# Debug.net
KiCad netlist of a schematic drawn in Altium Designer
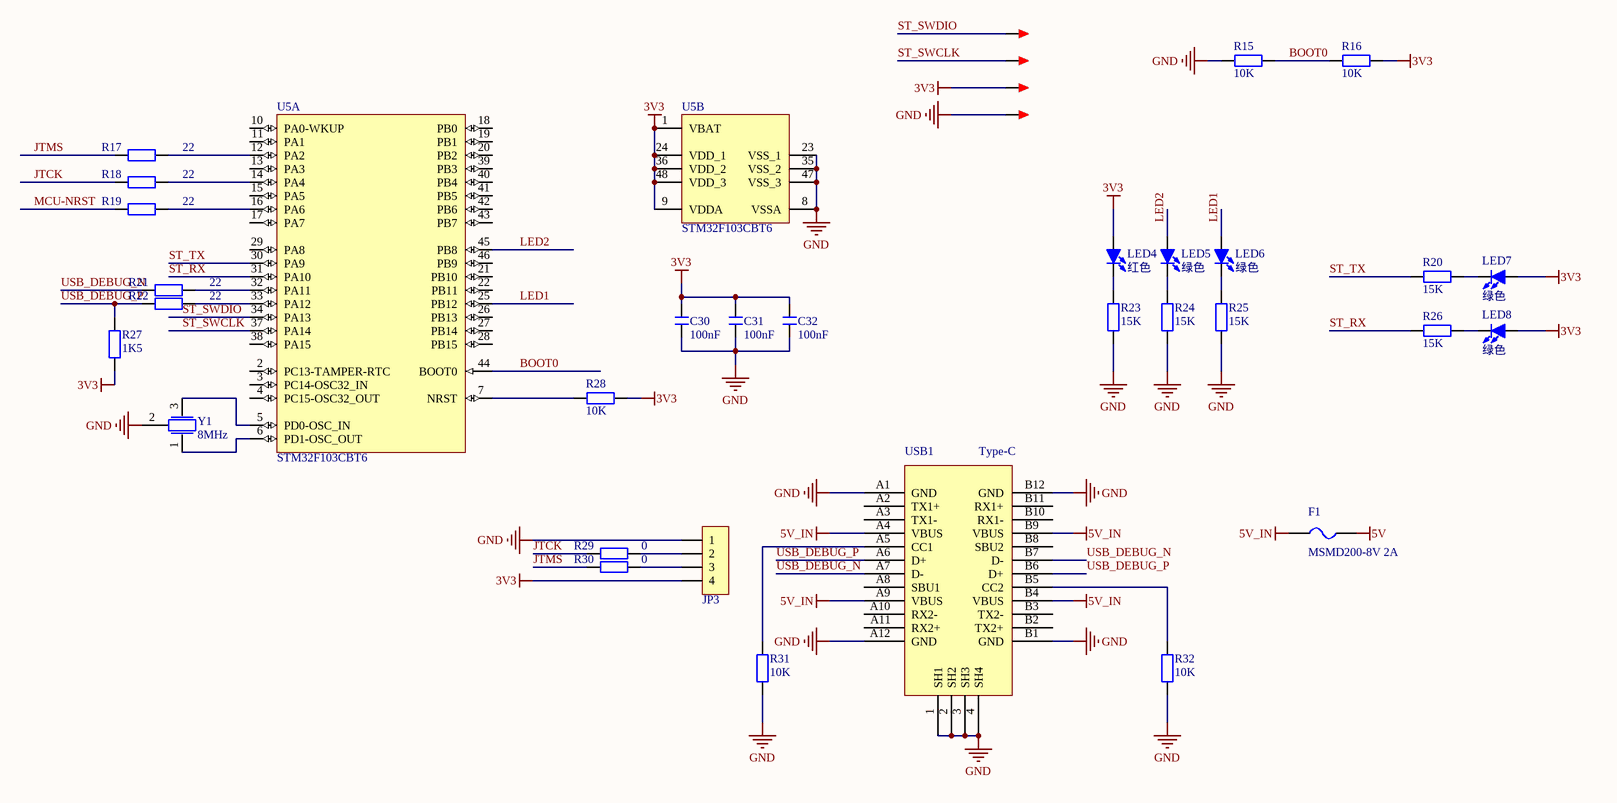
[diagram p0: Debug.SchDoc]

(export (version "E")
  (design (tool "Eeschema 10.0.6"))
  (components
    (comp (ref "C30")
      (value "100nF")
      (footprint "C 0402_L")
      (description "贴片电容")
      (libsource (lib "3.1   - 电阻-电容-电感") (part "C"))
    )
    (comp (ref "C31")
      (value "100nF")
      (footprint "C 0402_L")
      (description "贴片电容")
      (libsource (lib "3.1   - 电阻-电容-电感") (part "C"))
    )
    (comp (ref "C32")
      (value "100nF")
      (footprint "C 0402_L")
      (description "贴片电容")
      (libsource (lib "3.1   - 电阻-电容-电感") (part "C"))
    )
    (comp (ref "F1")
      (value "MSMD200-8V 2A")
      (footprint "FU 0603")
      (description "贴片保险丝")
      (libsource (lib "10.1 - 保险丝-晶振") (part "FU"))
    )
    (comp (ref "JP3")
      (value "HDR-1X4")
      (footprint "HDR2.54-WI-4P")
      (description "4P接插件")
      (libsource (lib "4.5   - 接插件-脚距2.54") (part "Header 4"))
    )
    (comp (ref "LED4")
      (value "红色")
      (footprint "LED")
      (description "C84267")
      (libsource (lib "9.1   - LED") (part "LED-SMD"))
    )
    (comp (ref "LED5")
      (value "绿色")
      (footprint "LED")
      (description "C84267")
      (libsource (lib "9.1   - LED") (part "LED-SMD"))
    )
    (comp (ref "LED6")
      (value "绿色")
      (footprint "LED")
      (description "C84267")
      (libsource (lib "9.1   - LED") (part "LED-SMD"))
    )
    (comp (ref "LED7")
      (value "绿色")
      (footprint "LED")
      (description "C84267")
      (libsource (lib "9.1   - LED") (part "LED-SMD"))
    )
    (comp (ref "LED8")
      (value "绿色")
      (footprint "LED")
      (description "C84267")
      (libsource (lib "9.1   - LED") (part "LED-SMD"))
    )
    (comp (ref "R15")
      (value "10K")
      (footprint "R 0402_L")
      (description "贴片电阻")
      (libsource (lib "3.1   - 电阻-电容-电感") (part "R"))
    )
    (comp (ref "R16")
      (value "10K")
      (footprint "R 0402_L")
      (description "贴片电阻")
      (libsource (lib "3.1   - 电阻-电容-电感") (part "R"))
    )
    (comp (ref "R17")
      (value "22")
      (footprint "R 0402_L")
      (description "贴片电阻")
      (libsource (lib "3.1   - 电阻-电容-电感") (part "R"))
    )
    (comp (ref "R18")
      (value "22")
      (footprint "R 0402_L")
      (description "贴片电阻")
      (libsource (lib "3.1   - 电阻-电容-电感") (part "R"))
    )
    (comp (ref "R19")
      (value "22")
      (footprint "R 0402_L")
      (description "贴片电阻")
      (libsource (lib "3.1   - 电阻-电容-电感") (part "R"))
    )
    (comp (ref "R20")
      (value "15K")
      (footprint "R 0402_L")
      (description "贴片电阻 0402 5%")
      (libsource (lib "3.1   - 电阻-电容-电感") (part "R"))
    )
    (comp (ref "R21")
      (value "22")
      (footprint "R 0402_L")
      (description "贴片电阻")
      (libsource (lib "3.1   - 电阻-电容-电感") (part "R"))
    )
    (comp (ref "R22")
      (value "22")
      (footprint "R 0402_L")
      (description "贴片电阻")
      (libsource (lib "3.1   - 电阻-电容-电感") (part "R"))
    )
    (comp (ref "R23")
      (value "15K")
      (footprint "R 0402_L")
      (description "贴片电阻 0402 5%")
      (libsource (lib "3.1   - 电阻-电容-电感") (part "R"))
    )
    (comp (ref "R24")
      (value "15K")
      (footprint "R 0402_L")
      (description "贴片电阻 0402 5%")
      (libsource (lib "3.1   - 电阻-电容-电感") (part "R"))
    )
    (comp (ref "R25")
      (value "15K")
      (footprint "R 0402_L")
      (description "贴片电阻 0402 5%")
      (libsource (lib "3.1   - 电阻-电容-电感") (part "R"))
    )
    (comp (ref "R26")
      (value "15K")
      (footprint "R 0402_L")
      (description "贴片电阻 0402 5%")
      (libsource (lib "3.1   - 电阻-电容-电感") (part "R"))
    )
    (comp (ref "R27")
      (value "1K5")
      (footprint "R 0402_L")
      (description "贴片电阻")
      (libsource (lib "3.1   - 电阻-电容-电感") (part "R"))
    )
    (comp (ref "R28")
      (value "10K")
      (footprint "R 0402_L")
      (description "贴片电阻")
      (libsource (lib "3.1   - 电阻-电容-电感") (part "R"))
    )
    (comp (ref "R29")
      (value "0")
      (footprint "R 0402_L")
      (description "贴片电阻")
      (libsource (lib "3.1   - 电阻-电容-电感") (part "R"))
    )
    (comp (ref "R30")
      (value "0")
      (footprint "R 0402_L")
      (description "贴片电阻")
      (libsource (lib "3.1   - 电阻-电容-电感") (part "R"))
    )
    (comp (ref "R31")
      (value "10K")
      (footprint "R 0402_L")
      (description "贴片电阻")
      (libsource (lib "3.1   - 电阻-电容-电感") (part "R"))
    )
    (comp (ref "R32")
      (value "10K")
      (footprint "R 0402_L")
      (description "贴片电阻")
      (libsource (lib "3.1   - 电阻-电容-电感") (part "R"))
    )
    (comp (ref "TP1")
      (value "TEST")
      (footprint "TEST 1.2")
      (description "测试点")
      (libsource (lib "15.1 - 未分类器件") (part "TEST"))
    )
    (comp (ref "TP2")
      (value "TEST")
      (footprint "TEST 1.2")
      (description "测试点")
      (libsource (lib "15.1 - 未分类器件") (part "TEST"))
    )
    (comp (ref "TP3")
      (value "TEST")
      (footprint "TEST 1.2")
      (description "测试点")
      (libsource (lib "15.1 - 未分类器件") (part "TEST"))
    )
    (comp (ref "TP4")
      (value "TEST")
      (footprint "TEST 1.2")
      (description "测试点")
      (libsource (lib "15.1 - 未分类器件") (part "TEST"))
    )
    (comp (ref "U5")
      (value "STM32F103CBT6")
      (footprint "LQFP48-7*7")
      (libsource (lib "STMicroelectronics STM32 F1") (part "STM32F103CBT6"))
    )
    (comp (ref "USB1")
      (value "Type-C")
      (footprint "Type-c接口")
      (libsource (lib "MyPcbLib") (part "USB-Type-C-TOP"))
    )
    (comp (ref "Y1")
      (value "8MHz")
      (footprint "三脚晶振")
      (description "村田贴片")
      (libsource (lib "MyPcbLib") (part "晶振-3Pin"))
    )
  )
  (nets
    (net (code "1") (name "/BOOT0") (class "Default")
      (node (ref "R15") (pin "2") (pinfunction "2_2") (pintype "passive"))
      (node (ref "R16") (pin "2") (pinfunction "2_2") (pintype "passive"))
      (node (ref "U5") (pin "44") (pinfunction "BOOT0_44") (pintype "input"))
    )
    (net (code "2") (name "/JTCK") (class "Default")
      (node (ref "R18") (pin "2") (pinfunction "2_2") (pintype "passive"))
      (node (ref "R29") (pin "1") (pinfunction "1_1") (pintype "passive"))
    )
    (net (code "3") (name "/JTMS") (class "Default")
      (node (ref "R17") (pin "2") (pinfunction "2_2") (pintype "passive"))
      (node (ref "R30") (pin "1") (pinfunction "1_1") (pintype "passive"))
    )
    (net (code "4") (name "/LED1") (class "Default")
      (node (ref "LED6") (pin "1") (pinfunction "A_1") (pintype "passive"))
      (node (ref "U5") (pin "25") (pinfunction "PB12_25") (pintype "bidirectional"))
    )
    (net (code "5") (name "/LED2") (class "Default")
      (node (ref "LED5") (pin "1") (pinfunction "A_1") (pintype "passive"))
      (node (ref "U5") (pin "45") (pinfunction "PB8_45") (pintype "bidirectional"))
    )
    (net (code "6") (name "/MCU-NRST") (class "Default")
      (node (ref "R19") (pin "2") (pinfunction "2_2") (pintype "passive"))
    )
    (net (code "7") (name "/ST_RX") (class "Default")
      (node (ref "R26") (pin "1") (pinfunction "1_1") (pintype "passive"))
      (node (ref "U5") (pin "31") (pinfunction "PA10_31") (pintype "bidirectional"))
    )
    (net (code "8") (name "/ST_SWCLK") (class "Default")
      (node (ref "TP2") (pin "1") (pinfunction "1_1") (pintype "passive"))
      (node (ref "U5") (pin "37") (pinfunction "PA14_37") (pintype "bidirectional"))
    )
    (net (code "9") (name "/ST_SWDIO") (class "Default")
      (node (ref "TP1") (pin "1") (pinfunction "1_1") (pintype "passive"))
      (node (ref "U5") (pin "34") (pinfunction "PA13_34") (pintype "bidirectional"))
    )
    (net (code "10") (name "/ST_TX") (class "Default")
      (node (ref "R20") (pin "1") (pinfunction "1_1") (pintype "passive"))
      (node (ref "U5") (pin "30") (pinfunction "PA9_30") (pintype "bidirectional"))
    )
    (net (code "11") (name "/USB_DEBUG_N") (class "Default")
      (node (ref "R21") (pin "2") (pinfunction "2_2") (pintype "passive"))
      (node (ref "USB1") (pin "A7") (pinfunction "D-_A7") (pintype "passive"))
      (node (ref "USB1") (pin "B7") (pinfunction "D-_B7") (pintype "passive"))
    )
    (net (code "12") (name "/USB_DEBUG_P") (class "Default")
      (node (ref "R22") (pin "2") (pinfunction "2_2") (pintype "passive"))
      (node (ref "R27") (pin "1") (pinfunction "1_1") (pintype "passive"))
      (node (ref "USB1") (pin "A6") (pinfunction "D+_A6") (pintype "passive"))
      (node (ref "USB1") (pin "B6") (pinfunction "D+_B6") (pintype "passive"))
    )
    (net (code "13") (name "3V3") (class "Default")
      (node (ref "C30") (pin "2") (pinfunction "2_2") (pintype "passive"))
      (node (ref "C31") (pin "2") (pinfunction "2_2") (pintype "passive"))
      (node (ref "C32") (pin "2") (pinfunction "2_2") (pintype "passive"))
      (node (ref "JP3") (pin "4") (pinfunction "4_4") (pintype "passive"))
      (node (ref "LED4") (pin "1") (pinfunction "A_1") (pintype "passive"))
      (node (ref "LED7") (pin "1") (pinfunction "A_1") (pintype "passive"))
      (node (ref "LED8") (pin "1") (pinfunction "A_1") (pintype "passive"))
      (node (ref "R16") (pin "1") (pinfunction "1_1") (pintype "passive"))
      (node (ref "R27") (pin "2") (pinfunction "2_2") (pintype "passive"))
      (node (ref "R28") (pin "1") (pinfunction "1_1") (pintype "passive"))
      (node (ref "TP3") (pin "1") (pinfunction "1_1") (pintype "passive"))
      (node (ref "U5") (pin "1") (pinfunction "VBAT_1") (pintype "power_in"))
      (node (ref "U5") (pin "24") (pinfunction "VDD_1_24") (pintype "power_in"))
      (node (ref "U5") (pin "36") (pinfunction "VDD_2_36") (pintype "power_in"))
      (node (ref "U5") (pin "48") (pinfunction "VDD_3_48") (pintype "power_in"))
      (node (ref "U5") (pin "9") (pinfunction "VDDA_9") (pintype "power_in"))
    )
    (net (code "14") (name "5V") (class "Default")
      (node (ref "F1") (pin "2") (pinfunction "2_2") (pintype "passive"))
    )
    (net (code "15") (name "5V_IN") (class "Default")
      (node (ref "F1") (pin "1") (pinfunction "1_1") (pintype "passive"))
      (node (ref "USB1") (pin "A4") (pinfunction "VBUS_A4") (pintype "passive"))
      (node (ref "USB1") (pin "A9") (pinfunction "VBUS_A9") (pintype "passive"))
      (node (ref "USB1") (pin "B4") (pinfunction "VBUS_B4") (pintype "passive"))
      (node (ref "USB1") (pin "B9") (pinfunction "VBUS_B9") (pintype "passive"))
    )
    (net (code "16") (name "GND") (class "Default")
      (node (ref "C30") (pin "1") (pinfunction "1_1") (pintype "passive"))
      (node (ref "C31") (pin "1") (pinfunction "1_1") (pintype "passive"))
      (node (ref "C32") (pin "1") (pinfunction "1_1") (pintype "passive"))
      (node (ref "JP3") (pin "1") (pinfunction "1_1") (pintype "passive"))
      (node (ref "R15") (pin "1") (pinfunction "1_1") (pintype "passive"))
      (node (ref "R23") (pin "1") (pinfunction "1_1") (pintype "passive"))
      (node (ref "R24") (pin "1") (pinfunction "1_1") (pintype "passive"))
      (node (ref "R25") (pin "1") (pinfunction "1_1") (pintype "passive"))
      (node (ref "R31") (pin "1") (pinfunction "1_1") (pintype "passive"))
      (node (ref "R32") (pin "1") (pinfunction "1_1") (pintype "passive"))
      (node (ref "TP4") (pin "1") (pinfunction "1_1") (pintype "passive"))
      (node (ref "U5") (pin "23") (pinfunction "VSS_1_23") (pintype "power_in"))
      (node (ref "U5") (pin "35") (pinfunction "VSS_2_35") (pintype "power_in"))
      (node (ref "U5") (pin "47") (pinfunction "VSS_3_47") (pintype "power_in"))
      (node (ref "U5") (pin "8") (pinfunction "VSSA_8") (pintype "power_in"))
      (node (ref "USB1") (pin "1") (pinfunction "SH1_1") (pintype "passive"))
      (node (ref "USB1") (pin "2") (pinfunction "SH2_2") (pintype "passive"))
      (node (ref "USB1") (pin "3") (pinfunction "SH3_3") (pintype "passive"))
      (node (ref "USB1") (pin "4") (pinfunction "SH4_4") (pintype "passive"))
      (node (ref "USB1") (pin "A1") (pinfunction "GND_A1") (pintype "passive"))
      (node (ref "USB1") (pin "A12") (pinfunction "GND_A12") (pintype "passive"))
      (node (ref "USB1") (pin "B1") (pinfunction "GND_B1") (pintype "passive"))
      (node (ref "USB1") (pin "B12") (pinfunction "GND_B12") (pintype "passive"))
      (node (ref "Y1") (pin "2") (pinfunction "2_2") (pintype "passive"))
    )
    (net (code "17") (name "Net-(JP3-Pad2)") (class "Default")
      (node (ref "JP3") (pin "2") (pinfunction "2_2") (pintype "passive"))
      (node (ref "R29") (pin "2") (pinfunction "2_2") (pintype "passive"))
    )
    (net (code "18") (name "Net-(JP3-Pad3)") (class "Default")
      (node (ref "JP3") (pin "3") (pinfunction "3_3") (pintype "passive"))
      (node (ref "R30") (pin "2") (pinfunction "2_2") (pintype "passive"))
    )
    (net (code "19") (name "Net-(LED4-K)") (class "Default")
      (node (ref "LED4") (pin "2") (pinfunction "K_2") (pintype "passive"))
      (node (ref "R23") (pin "2") (pinfunction "2_2") (pintype "passive"))
    )
    (net (code "20") (name "Net-(LED5-K)") (class "Default")
      (node (ref "LED5") (pin "2") (pinfunction "K_2") (pintype "passive"))
      (node (ref "R24") (pin "2") (pinfunction "2_2") (pintype "passive"))
    )
    (net (code "21") (name "Net-(LED6-K)") (class "Default")
      (node (ref "LED6") (pin "2") (pinfunction "K_2") (pintype "passive"))
      (node (ref "R25") (pin "2") (pinfunction "2_2") (pintype "passive"))
    )
    (net (code "22") (name "Net-(LED7-K)") (class "Default")
      (node (ref "LED7") (pin "2") (pinfunction "K_2") (pintype "passive"))
      (node (ref "R20") (pin "2") (pinfunction "2_2") (pintype "passive"))
    )
    (net (code "23") (name "Net-(LED8-K)") (class "Default")
      (node (ref "LED8") (pin "2") (pinfunction "K_2") (pintype "passive"))
      (node (ref "R26") (pin "2") (pinfunction "2_2") (pintype "passive"))
    )
    (net (code "24") (name "Net-(U5A-NRST)") (class "Default")
      (node (ref "R28") (pin "2") (pinfunction "2_2") (pintype "passive"))
      (node (ref "U5") (pin "7") (pinfunction "NRST_7") (pintype "bidirectional"))
    )
    (net (code "25") (name "Net-(U5A-PA2)") (class "Default")
      (node (ref "R17") (pin "1") (pinfunction "1_1") (pintype "passive"))
      (node (ref "U5") (pin "12") (pinfunction "PA2_12") (pintype "bidirectional"))
    )
    (net (code "26") (name "Net-(U5A-PA4)") (class "Default")
      (node (ref "R18") (pin "1") (pinfunction "1_1") (pintype "passive"))
      (node (ref "U5") (pin "14") (pinfunction "PA4_14") (pintype "bidirectional"))
    )
    (net (code "27") (name "Net-(U5A-PA6)") (class "Default")
      (node (ref "R19") (pin "1") (pinfunction "1_1") (pintype "passive"))
      (node (ref "U5") (pin "16") (pinfunction "PA6_16") (pintype "bidirectional"))
    )
    (net (code "28") (name "Net-(U5A-PA11)") (class "Default")
      (node (ref "R21") (pin "1") (pinfunction "1_1") (pintype "passive"))
      (node (ref "U5") (pin "32") (pinfunction "PA11_32") (pintype "bidirectional"))
    )
    (net (code "29") (name "Net-(U5A-PA12)") (class "Default")
      (node (ref "R22") (pin "1") (pinfunction "1_1") (pintype "passive"))
      (node (ref "U5") (pin "33") (pinfunction "PA12_33") (pintype "bidirectional"))
    )
    (net (code "30") (name "Net-(U5A-PD0-OSC_IN)") (class "Default")
      (node (ref "U5") (pin "5") (pinfunction "PD0-OSC_IN_5") (pintype "bidirectional"))
      (node (ref "Y1") (pin "3") (pinfunction "3_3") (pintype "passive"))
    )
    (net (code "31") (name "Net-(U5A-PD1-OSC_OUT)") (class "Default")
      (node (ref "U5") (pin "6") (pinfunction "PD1-OSC_OUT_6") (pintype "bidirectional"))
      (node (ref "Y1") (pin "1") (pinfunction "1_1") (pintype "passive"))
    )
    (net (code "32") (name "Net-(USB1-CC1)") (class "Default")
      (node (ref "R31") (pin "2") (pinfunction "2_2") (pintype "passive"))
      (node (ref "USB1") (pin "A5") (pinfunction "CC1_A5") (pintype "passive"))
    )
    (net (code "33") (name "Net-(USB1-CC2)") (class "Default")
      (node (ref "R32") (pin "2") (pinfunction "2_2") (pintype "passive"))
      (node (ref "USB1") (pin "B5") (pinfunction "CC2_B5") (pintype "passive"))
    )
    (net (code "34") (name "unconnected-(U5A-PA0-WKUP-Pad10)") (class "Default")
      (node (ref "U5") (pin "10") (pinfunction "PA0-WKUP_10") (pintype "bidirectional"))
    )
    (net (code "35") (name "unconnected-(U5A-PA1-Pad11)") (class "Default")
      (node (ref "U5") (pin "11") (pinfunction "PA1_11") (pintype "bidirectional"))
    )
    (net (code "36") (name "unconnected-(U5A-PA3-Pad13)") (class "Default")
      (node (ref "U5") (pin "13") (pinfunction "PA3_13") (pintype "bidirectional"))
    )
    (net (code "37") (name "unconnected-(U5A-PA5-Pad15)") (class "Default")
      (node (ref "U5") (pin "15") (pinfunction "PA5_15") (pintype "bidirectional"))
    )
    (net (code "38") (name "unconnected-(U5A-PA7-Pad17)") (class "Default")
      (node (ref "U5") (pin "17") (pinfunction "PA7_17") (pintype "bidirectional"))
    )
    (net (code "39") (name "unconnected-(U5A-PA8-Pad29)") (class "Default")
      (node (ref "U5") (pin "29") (pinfunction "PA8_29") (pintype "bidirectional"))
    )
    (net (code "40") (name "unconnected-(U5A-PA15-Pad38)") (class "Default")
      (node (ref "U5") (pin "38") (pinfunction "PA15_38") (pintype "bidirectional"))
    )
    (net (code "41") (name "unconnected-(U5A-PB0-Pad18)") (class "Default")
      (node (ref "U5") (pin "18") (pinfunction "PB0_18") (pintype "bidirectional"))
    )
    (net (code "42") (name "unconnected-(U5A-PB1-Pad19)") (class "Default")
      (node (ref "U5") (pin "19") (pinfunction "PB1_19") (pintype "bidirectional"))
    )
    (net (code "43") (name "unconnected-(U5A-PB2-Pad20)") (class "Default")
      (node (ref "U5") (pin "20") (pinfunction "PB2_20") (pintype "bidirectional"))
    )
    (net (code "44") (name "unconnected-(U5A-PB3-Pad39)") (class "Default")
      (node (ref "U5") (pin "39") (pinfunction "PB3_39") (pintype "bidirectional"))
    )
    (net (code "45") (name "unconnected-(U5A-PB4-Pad40)") (class "Default")
      (node (ref "U5") (pin "40") (pinfunction "PB4_40") (pintype "bidirectional"))
    )
    (net (code "46") (name "unconnected-(U5A-PB5-Pad41)") (class "Default")
      (node (ref "U5") (pin "41") (pinfunction "PB5_41") (pintype "bidirectional"))
    )
    (net (code "47") (name "unconnected-(U5A-PB6-Pad42)") (class "Default")
      (node (ref "U5") (pin "42") (pinfunction "PB6_42") (pintype "bidirectional"))
    )
    (net (code "48") (name "unconnected-(U5A-PB7-Pad43)") (class "Default")
      (node (ref "U5") (pin "43") (pinfunction "PB7_43") (pintype "bidirectional"))
    )
    (net (code "49") (name "unconnected-(U5A-PB9-Pad46)") (class "Default")
      (node (ref "U5") (pin "46") (pinfunction "PB9_46") (pintype "bidirectional"))
    )
    (net (code "50") (name "unconnected-(U5A-PB10-Pad21)") (class "Default")
      (node (ref "U5") (pin "21") (pinfunction "PB10_21") (pintype "bidirectional"))
    )
    (net (code "51") (name "unconnected-(U5A-PB11-Pad22)") (class "Default")
      (node (ref "U5") (pin "22") (pinfunction "PB11_22") (pintype "bidirectional"))
    )
    (net (code "52") (name "unconnected-(U5A-PB13-Pad26)") (class "Default")
      (node (ref "U5") (pin "26") (pinfunction "PB13_26") (pintype "bidirectional"))
    )
    (net (code "53") (name "unconnected-(U5A-PB14-Pad27)") (class "Default")
      (node (ref "U5") (pin "27") (pinfunction "PB14_27") (pintype "bidirectional"))
    )
    (net (code "54") (name "unconnected-(U5A-PB15-Pad28)") (class "Default")
      (node (ref "U5") (pin "28") (pinfunction "PB15_28") (pintype "bidirectional"))
    )
    (net (code "55") (name "unconnected-(U5A-PC13-TAMPER-RTC-Pad2)") (class "Default")
      (node (ref "U5") (pin "2") (pinfunction "PC13-TAMPER-RTC_2") (pintype "bidirectional"))
    )
    (net (code "56") (name "unconnected-(U5A-PC14-OSC32_IN-Pad3)") (class "Default")
      (node (ref "U5") (pin "3") (pinfunction "PC14-OSC32_IN_3") (pintype "bidirectional"))
    )
    (net (code "57") (name "unconnected-(U5A-PC15-OSC32_OUT-Pad4)") (class "Default")
      (node (ref "U5") (pin "4") (pinfunction "PC15-OSC32_OUT_4") (pintype "bidirectional"))
    )
    (net (code "58") (name "unconnected-(USB1-RX1+-PadB11)") (class "Default")
      (node (ref "USB1") (pin "B11") (pinfunction "RX1+_B11") (pintype "passive"))
    )
    (net (code "59") (name "unconnected-(USB1-RX1--PadB10)") (class "Default")
      (node (ref "USB1") (pin "B10") (pinfunction "RX1-_B10") (pintype "passive"))
    )
    (net (code "60") (name "unconnected-(USB1-RX2+-PadA11)") (class "Default")
      (node (ref "USB1") (pin "A11") (pinfunction "RX2+_A11") (pintype "passive"))
    )
    (net (code "61") (name "unconnected-(USB1-RX2--PadA10)") (class "Default")
      (node (ref "USB1") (pin "A10") (pinfunction "RX2-_A10") (pintype "passive"))
    )
    (net (code "62") (name "unconnected-(USB1-SBU1-PadA8)") (class "Default")
      (node (ref "USB1") (pin "A8") (pinfunction "SBU1_A8") (pintype "passive"))
    )
    (net (code "63") (name "unconnected-(USB1-SBU2-PadB8)") (class "Default")
      (node (ref "USB1") (pin "B8") (pinfunction "SBU2_B8") (pintype "passive"))
    )
    (net (code "64") (name "unconnected-(USB1-TX1+-PadA2)") (class "Default")
      (node (ref "USB1") (pin "A2") (pinfunction "TX1+_A2") (pintype "passive"))
    )
    (net (code "65") (name "unconnected-(USB1-TX1--PadA3)") (class "Default")
      (node (ref "USB1") (pin "A3") (pinfunction "TX1-_A3") (pintype "passive"))
    )
    (net (code "66") (name "unconnected-(USB1-TX2+-PadB2)") (class "Default")
      (node (ref "USB1") (pin "B2") (pinfunction "TX2+_B2") (pintype "passive"))
    )
    (net (code "67") (name "unconnected-(USB1-TX2--PadB3)") (class "Default")
      (node (ref "USB1") (pin "B3") (pinfunction "TX2-_B3") (pintype "passive"))
    )
  )
)
